# main.net
KiCad netlist of a schematic drawn in Altium Designer
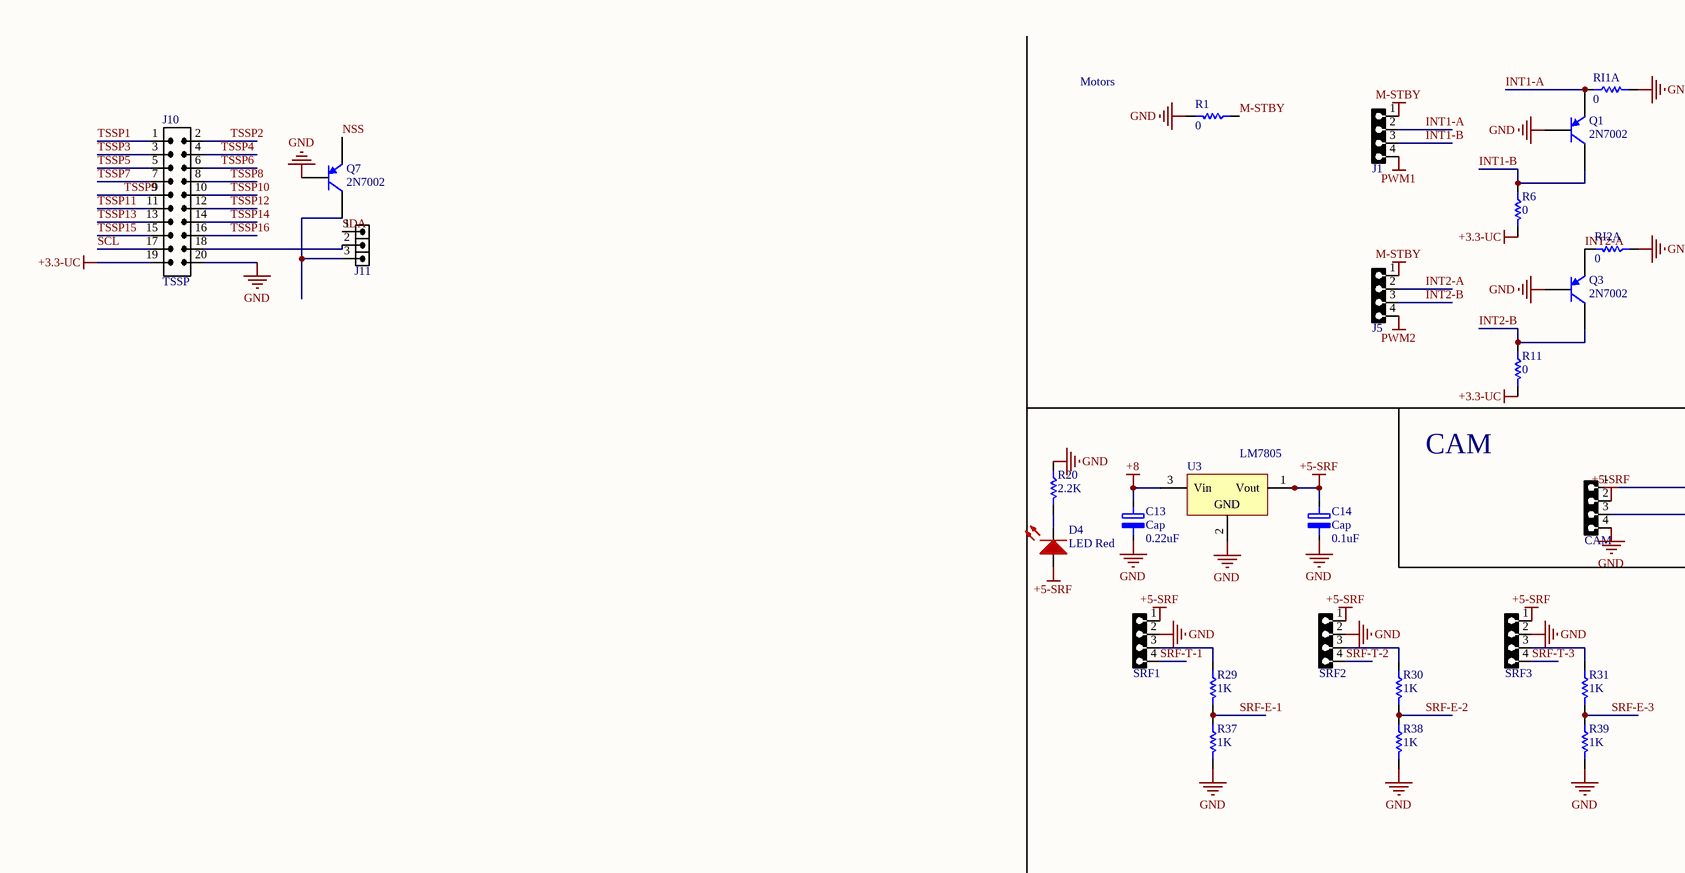
[diagram p0: main.SchDoc, top left]
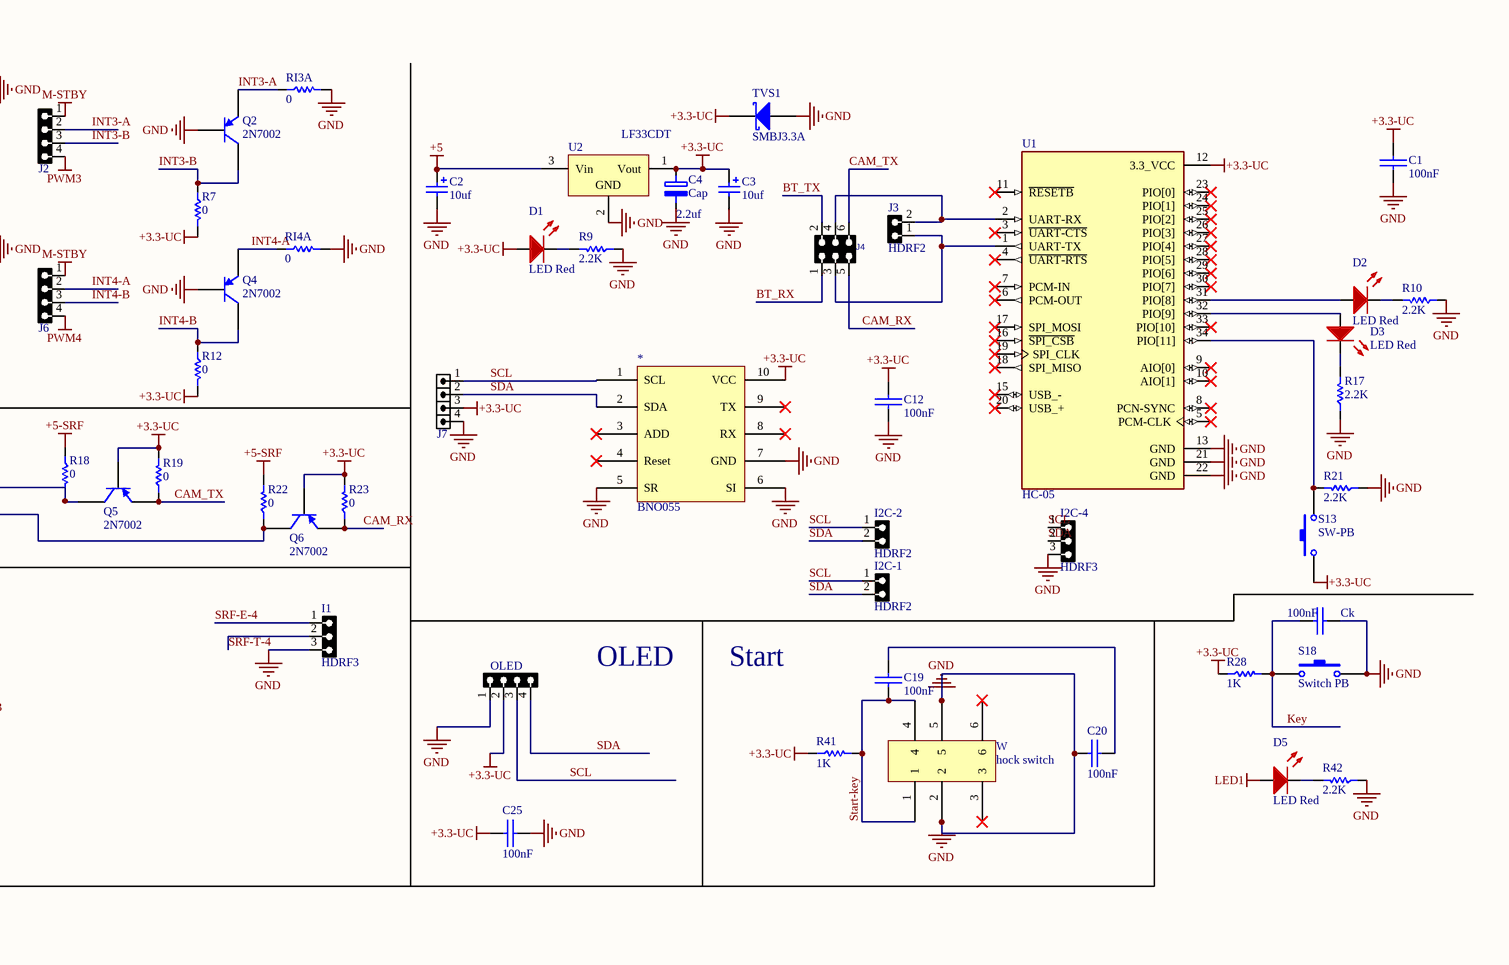
[diagram p1: main.SchDoc, top right]
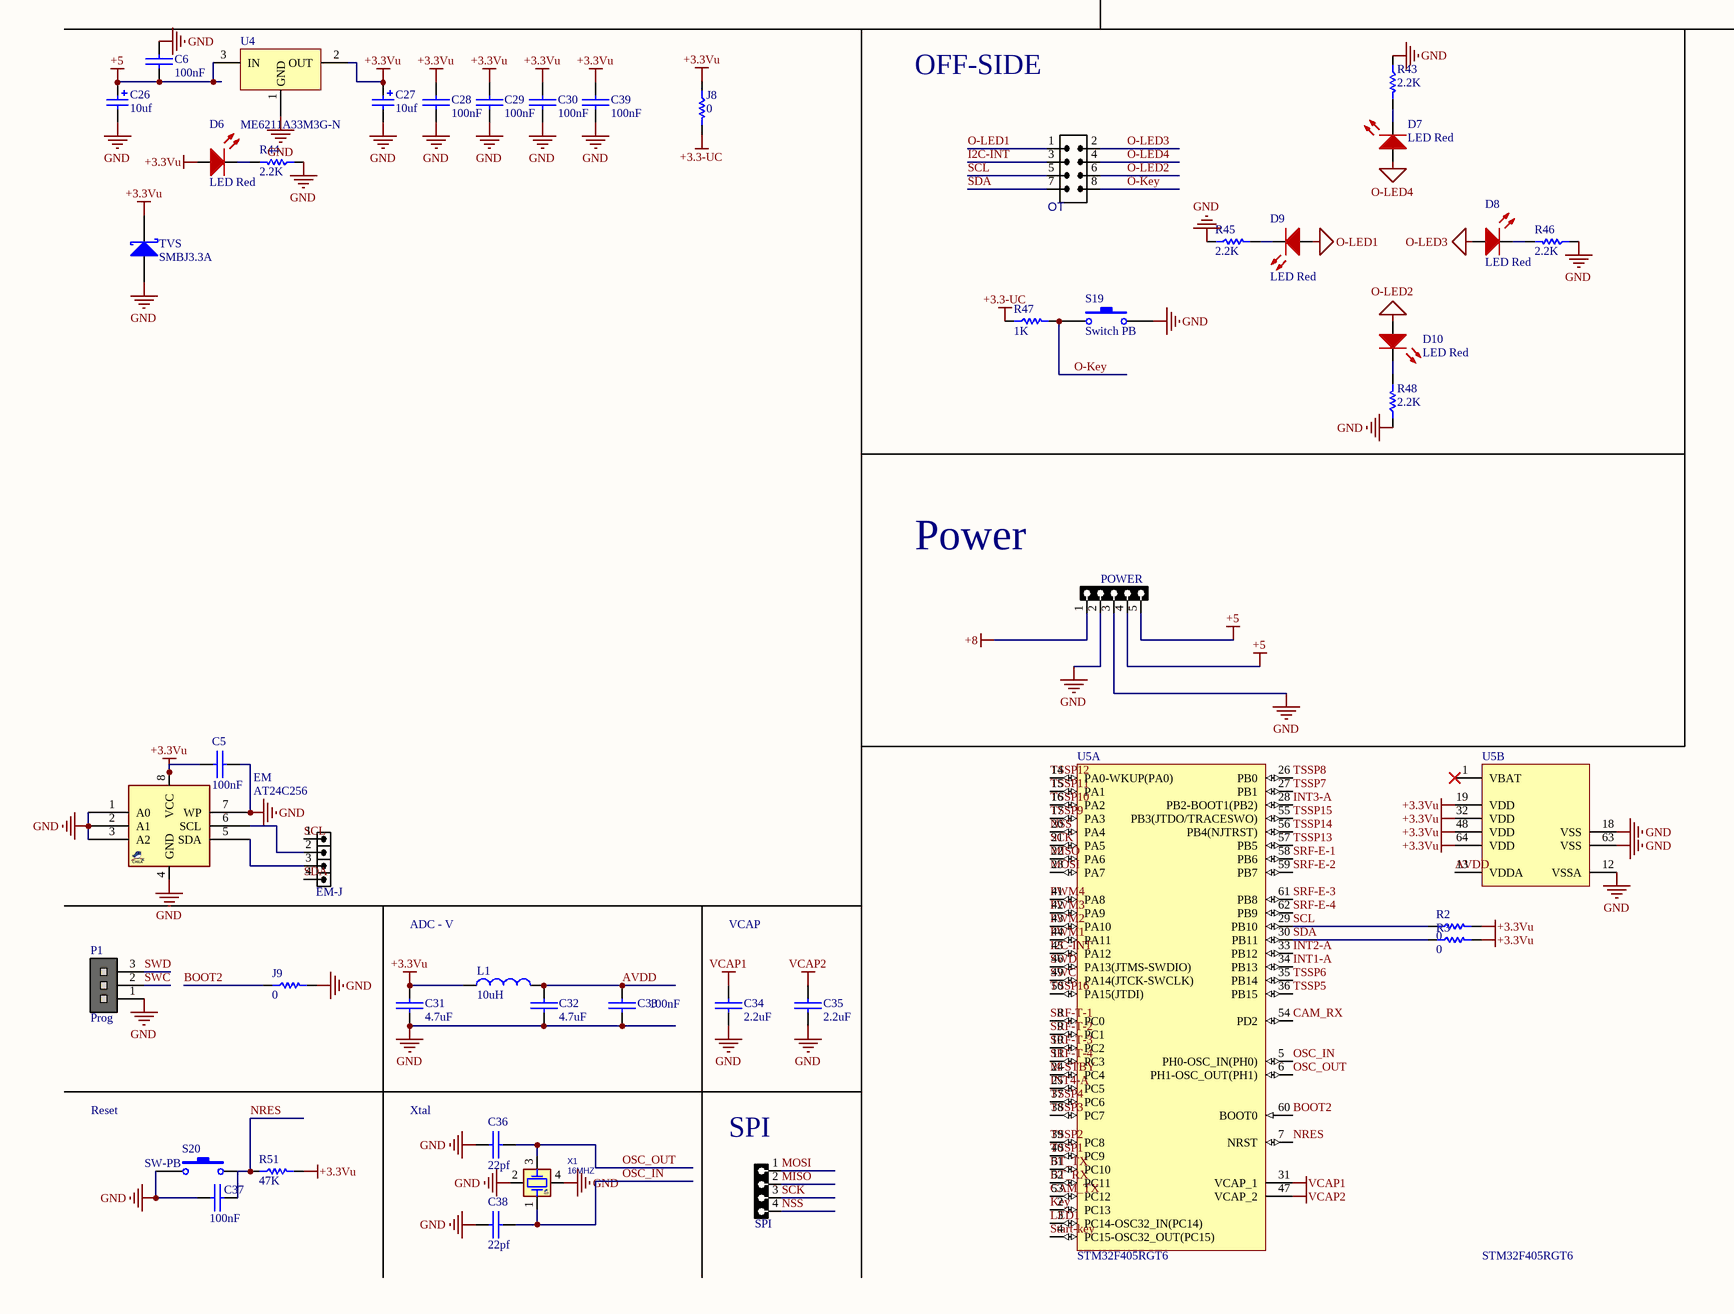
[diagram p2: main.SchDoc, bottom left]

(export (version "E")
  (design (tool "Eeschema 10.0.6"))
  (components
    (comp (ref "*") (value "BNO055") (footprint "BNO055") (libsource (lib "MA01") (part "BNO055")))
    (comp (ref "C1")
      (value "100nF")
      (footprint "SMD_CAP_0805")
      (description "Bipolar Capacitor")
      (fields (field (name "VOLTAGE") "100V") (field (name "DESIGNER") "Saeid Jorablo"))
      (libsource (lib "My Library") (part "Cap-Bipolar"))
    )
    (comp (ref "C2")
      (value "10uf")
      (footprint "Cap_A")
      (description "Solid Tantalum Chip Capacitor, Standard T491 Series - Industrial Grade")
      (fields (field (name "Comment") "Cap_tan") (field (name "PUBLISHER") "Altium Limited"))
      (libsource (lib "AYRIC Library") (part "Tantalum Cap"))
    )
    (comp (ref "C3")
      (value "10uf")
      (footprint "Cap_A")
      (description "Solid Tantalum Chip Capacitor, Standard T491 Series - Industrial Grade")
      (fields (field (name "Comment") "Cap_tan") (field (name "PUBLISHER") "Altium Limited"))
      (libsource (lib "AYRIC Library") (part "Tantalum Cap"))
    )
    (comp (ref "C4")
      (value "Cap")
      (footprint "Cap_E")
      (description "Polarized Capacitor (Radial)")
      (fields (field (name "ALTIUM_VALUE") "2.2uf"))
      (libsource (lib "AYRIC Library") (part "Cap_pol"))
    )
    (comp (ref "C5")
      (value "100nF")
      (footprint "C0603")
      (description "Bipolar Capacitor")
      (fields (field (name "VOLTAGE") "100V") (field (name "DESIGNER") "Saeid Jorablo"))
      (libsource (lib "My Library") (part "Cap-Bipolar"))
    )
    (comp (ref "C6")
      (value "100nF")
      (footprint "SMD_CAP_0805")
      (description "Bipolar Capacitor")
      (fields (field (name "VOLTAGE") "100V") (field (name "DESIGNER") "Saeid Jorablo"))
      (libsource (lib "My Library") (part "Cap-Bipolar"))
    )
    (comp (ref "C12")
      (value "100nF")
      (footprint "SMD_CAP_0805")
      (description "Bipolar Capacitor")
      (fields (field (name "VOLTAGE") "100V") (field (name "DESIGNER") "Saeid Jorablo"))
      (libsource (lib "My Library") (part "Cap-Bipolar"))
    )
    (comp (ref "C13")
      (value "Cap")
      (footprint "Cap1_(2mm)")
      (description "Polarized Capacitor (Radial)")
      (fields (field (name "C13") "0.22uF"))
      (libsource (lib "AYRIC Library") (part "Cap_pol"))
    )
    (comp (ref "C14")
      (value "Cap")
      (footprint "Cap1_(2mm)")
      (description "Polarized Capacitor (Radial)")
      (fields (field (name "C14") "0.1uF"))
      (libsource (lib "AYRIC Library") (part "Cap_pol"))
    )
    (comp (ref "C19")
      (value "100nF")
      (footprint "SMD_CAP_0805")
      (description "Bipolar Capacitor")
      (fields (field (name "VOLTAGE") "100V") (field (name "DESIGNER") "Saeid Jorablo"))
      (libsource (lib "My Library") (part "Cap-Bipolar"))
    )
    (comp (ref "C20")
      (value "100nF")
      (footprint "SMD_CAP_0805")
      (description "Bipolar Capacitor")
      (fields (field (name "VOLTAGE") "100V") (field (name "DESIGNER") "Saeid Jorablo"))
      (libsource (lib "My Library") (part "Cap-Bipolar"))
    )
    (comp (ref "C25")
      (value "100nF")
      (footprint "SMD_CAP_0805")
      (description "Bipolar Capacitor")
      (fields (field (name "VOLTAGE") "100V") (field (name "DESIGNER") "Saeid Jorablo"))
      (libsource (lib "My Library") (part "Cap-Bipolar"))
    )
    (comp (ref "C26")
      (value "10uf")
      (footprint "Cap_A")
      (description "Solid Tantalum Chip Capacitor, Standard T491 Series - Industrial Grade")
      (fields (field (name "Comment") "Cap_tan") (field (name "PUBLISHER") "Altium Limited"))
      (libsource (lib "AYRIC Library") (part "Tantalum Cap"))
    )
    (comp (ref "C27")
      (value "10uf")
      (footprint "Cap_A")
      (description "Solid Tantalum Chip Capacitor, Standard T491 Series - Industrial Grade")
      (fields (field (name "Comment") "Cap_tan") (field (name "PUBLISHER") "Altium Limited"))
      (libsource (lib "AYRIC Library") (part "Tantalum Cap"))
    )
    (comp (ref "C28")
      (value "100nF")
      (footprint "C0603")
      (description "Bipolar Capacitor")
      (fields (field (name "VOLTAGE") "100V") (field (name "DESIGNER") "Saeid Jorablo"))
      (libsource (lib "My Library") (part "Cap-Bipolar"))
    )
    (comp (ref "C29")
      (value "100nF")
      (footprint "C0603")
      (description "Bipolar Capacitor")
      (fields (field (name "VOLTAGE") "100V") (field (name "DESIGNER") "Saeid Jorablo"))
      (libsource (lib "My Library") (part "Cap-Bipolar"))
    )
    (comp (ref "C30")
      (value "100nF")
      (footprint "C0603")
      (description "Bipolar Capacitor")
      (fields (field (name "VOLTAGE") "100V") (field (name "DESIGNER") "Saeid Jorablo"))
      (libsource (lib "My Library") (part "Cap-Bipolar"))
    )
    (comp (ref "C31")
      (value "4.7uF")
      (footprint "SMD_CAP_0805")
      (description "Bipolar Capacitor")
      (fields (field (name "VOLTAGE") "100V") (field (name "DESIGNER") "Saeid Jorablo"))
      (libsource (lib "My Library") (part "Cap-Bipolar"))
    )
    (comp (ref "C32")
      (value "4.7uF")
      (footprint "SMD_CAP_0805")
      (description "Bipolar Capacitor")
      (fields (field (name "VOLTAGE") "100V") (field (name "DESIGNER") "Saeid Jorablo"))
      (libsource (lib "My Library") (part "Cap-Bipolar"))
    )
    (comp (ref "C33")
      (value "100nF")
      (footprint "SMD_CAP_0805")
      (description "Bipolar Capacitor")
      (fields (field (name "VOLTAGE") "100V") (field (name "DESIGNER") "Saeid Jorablo"))
      (libsource (lib "My Library") (part "Cap-Bipolar"))
    )
    (comp (ref "C34")
      (value "2.2uF")
      (footprint "C0603")
      (description "Bipolar Capacitor")
      (fields (field (name "VOLTAGE") "100V") (field (name "DESIGNER") "Saeid Jorablo"))
      (libsource (lib "My Library") (part "Cap-Bipolar"))
    )
    (comp (ref "C35")
      (value "2.2uF")
      (footprint "C0603")
      (description "Bipolar Capacitor")
      (fields (field (name "VOLTAGE") "100V") (field (name "DESIGNER") "Saeid Jorablo"))
      (libsource (lib "My Library") (part "Cap-Bipolar"))
    )
    (comp (ref "C36")
      (value "22pf")
      (footprint "SMD_CAP_0805")
      (description "Bipolar Capacitor")
      (fields (field (name "VOLTAGE") "100V") (field (name "DESIGNER") "Saeid Jorablo"))
      (libsource (lib "My Library") (part "Cap-Bipolar"))
    )
    (comp (ref "C37")
      (value "100nF")
      (footprint "SMD_CAP_0805")
      (description "Bipolar Capacitor")
      (fields (field (name "VOLTAGE") "100V") (field (name "DESIGNER") "Saeid Jorablo"))
      (libsource (lib "My Library") (part "Cap-Bipolar"))
    )
    (comp (ref "C38")
      (value "22pf")
      (footprint "SMD_CAP_0805")
      (description "Bipolar Capacitor")
      (fields (field (name "VOLTAGE") "100V") (field (name "DESIGNER") "Saeid Jorablo"))
      (libsource (lib "My Library") (part "Cap-Bipolar"))
    )
    (comp (ref "C39")
      (value "100nF")
      (footprint "C0603")
      (description "Bipolar Capacitor")
      (fields (field (name "VOLTAGE") "100V") (field (name "DESIGNER") "Saeid Jorablo"))
      (libsource (lib "My Library") (part "Cap-Bipolar"))
    )
    (comp (ref "CAM")
      (value "HDRF4")
      (footprint "HDR_F_1X4")
      (description "CONN, HEADER, Female, pitch: 2.54mm, 4POS")
      (libsource (lib "conn_header") (part "HDR_F_1X4"))
    )
    (comp (ref "Ck")
      (value "100nF")
      (footprint "SMD_CAP_0805")
      (description "Bipolar Capacitor")
      (fields (field (name "VOLTAGE") "100V") (field (name "DESIGNER") "Saeid Jorablo"))
      (libsource (lib "My Library") (part "Cap-Bipolar"))
    )
    (comp (ref "D1")
      (value "LED Red")
      (footprint "LED_Red_1206")
      (libsource (lib "AYRIC Library") (part "LED Red"))
    )
    (comp (ref "D2")
      (value "LED Red")
      (footprint "LED_Red_1206")
      (libsource (lib "AYRIC Library") (part "LED Red"))
    )
    (comp (ref "D3")
      (value "LED Red")
      (footprint "LED_Red_1206")
      (libsource (lib "AYRIC Library") (part "LED Red"))
    )
    (comp (ref "D4")
      (value "LED Red")
      (footprint "LED_Red_1206")
      (libsource (lib "AYRIC Library") (part "LED Red"))
    )
    (comp (ref "D5")
      (value "LED Red")
      (footprint "LED_Red_1206")
      (libsource (lib "AYRIC Library") (part "LED Red"))
    )
    (comp (ref "D6")
      (value "LED Red")
      (footprint "LED_Red_1206")
      (libsource (lib "AYRIC Library") (part "LED Red"))
    )
    (comp (ref "D7")
      (value "LED Red")
      (footprint "LED_Red_1206")
      (libsource (lib "AYRIC Library") (part "LED Red"))
    )
    (comp (ref "D8")
      (value "LED Red")
      (footprint "LED_Red_1206")
      (libsource (lib "AYRIC Library") (part "LED Red"))
    )
    (comp (ref "D9")
      (value "LED Red")
      (footprint "LED_Red_1206")
      (libsource (lib "AYRIC Library") (part "LED Red"))
    )
    (comp (ref "D10")
      (value "LED Red")
      (footprint "LED_Red_1206")
      (libsource (lib "AYRIC Library") (part "LED Red"))
    )
    (comp (ref "EM")
      (value "AT24C256")
      (footprint "SO_8")
      (description "EEPROM, I2C")
      (libsource (lib "memory_eeprom_I2C") (part "EEPROM_I2C_AT24C256_SOP8"))
    )
    (comp (ref "EM-J")
      (value "HDR4")
      (footprint "HDR1SE_M_1X4")
      (description "HEADER, 1mm pitch, test, SMD")
      (libsource (lib "conn_header") (part "HDRTST_1X4"))
    )
    (comp (ref "I1")
      (value "HDRF3")
      (footprint "HDR_F_1X3")
      (description "CONN, HEADER, Female, pitch: 2.54mm, 3POS")
      (libsource (lib "conn_header") (part "HDR_F_1X3"))
    )
    (comp (ref "I2C-1")
      (value "HDRF2")
      (footprint "HDR_F_1X2")
      (description "CONN, HEADER, Female, pitch: 2.54mm, 2POS")
      (libsource (lib "") (part "HDR_F_1X2_1"))
    )
    (comp (ref "I2C-2")
      (value "HDRF2")
      (footprint "HDR_F_1X2")
      (description "CONN, HEADER, Female, pitch: 2.54mm, 2POS")
      (libsource (lib "") (part "HDR_F_1X2_1"))
    )
    (comp (ref "I2C-4")
      (value "HDRF3")
      (footprint "HDR_F_1X3")
      (description "CONN, HEADER, Female, pitch: 2.54mm, 3POS")
      (libsource (lib "conn_header") (part "HDR_F_1X3"))
    )
    (comp (ref "J1")
      (value "HDRF4")
      (footprint "HDR_F_1X4")
      (description "CONN, HEADER, Female, pitch: 2.54mm, 4POS")
      (libsource (lib "conn_header") (part "HDR_F_1X4"))
    )
    (comp (ref "J2")
      (value "HDRF4")
      (footprint "HDR_F_1X4")
      (description "CONN, HEADER, Female, pitch: 2.54mm, 4POS")
      (libsource (lib "conn_header") (part "HDR_F_1X4"))
    )
    (comp (ref "J3")
      (value "HDRF2")
      (footprint "HDR_F_1X2")
      (description "CONN, HEADER, Female, pitch: 2.54mm, 2POS")
      (libsource (lib "conn_header") (part "HDR_F_1X2"))
    )
    (comp (ref "J4")
      (value "HDRF_2X3")
      (footprint "HDR_F_2X3")
      (description "CONN, HEADER, Female, pitch: 2.54mm, 6POS")
      (fields (field (name "MANF_P#") "MANF_PART#") (field (name "MANF") "MANF"))
      (libsource (lib "conn_header") (part "HDR_F_2X3"))
    )
    (comp (ref "J5")
      (value "HDRF4")
      (footprint "HDR_F_1X4")
      (description "CONN, HEADER, Female, pitch: 2.54mm, 4POS")
      (libsource (lib "conn_header") (part "HDR_F_1X4"))
    )
    (comp (ref "J6")
      (value "HDRF4")
      (footprint "HDR_F_1X4")
      (description "CONN, HEADER, Female, pitch: 2.54mm, 4POS")
      (libsource (lib "conn_header") (part "HDR_F_1X4"))
    )
    (comp (ref "J7")
      (value "HDR1X4")
      (footprint "HDR_M_1X4")
      (description "CONN, HEADER, Male, pitch: 2.54mm, 4POS")
      (libsource (lib "conn_header") (part "HDR_M_1X4"))
    )
    (comp (ref "J8")
      (value "0")
      (footprint "RES 0805 (2012X06L)")
      (description "Resistor")
      (libsource (lib "My Library") (part "Resistor"))
    )
    (comp (ref "J9")
      (value "0")
      (footprint "RES 0603 (1608X06L)")
      (description "Resistor")
      (libsource (lib "My Library") (part "Resistor"))
    )
    (comp (ref "J10")
      (value "TSSP")
      (footprint "IDC_2X10")
      (description "CONN, IDC, Male, pitch: 2.54mm, 20POS")
      (libsource (lib "conn_header_idc") (part "IDC_2X10"))
    )
    (comp (ref "J11")
      (value "HDR3")
      (footprint "HDR1SE_M_1X3")
      (description "HEADER, 1mm pitch, test, SMD")
      (libsource (lib "conn_header") (part "HDRTST_1X3"))
    )
    (comp (ref "L1")
      (value "10uH")
      (footprint "Capacitor_805")
      (fields (field (name "Comment") "Inductor") (field (name "PUBLISHER") "Altium Limited"))
      (libsource (lib "AYRIC Library") (part "Inductor"))
    )
    (comp (ref "OLED")
      (value "HDRF4")
      (footprint "OLED64*128")
      (description "CONN, HEADER, Female, pitch: 2.54mm, 4POS")
      (libsource (lib "") (part "HDR_F_1X4_1"))
    )
    (comp (ref "OT")
      (value "IDC_2X4")
      (footprint "IDC_2X4")
      (description "CONN, IDC, Male, pitch: 2.54mm, 8POS")
      (libsource (lib "conn_header_idc") (part "IDC_2X4"))
    )
    (comp (ref "P1")
      (value "Prog")
      (footprint "HDR 1X3")
      (description "Header, 3-Pin")
      (libsource (lib "Ayric connectors") (part "Header 3"))
    )
    (comp (ref "POWER")
      (value "HDRF5")
      (footprint "HDR_F_1X5")
      (description "CONN, HEADER, Female, pitch: 2.54mm, 5POS")
      (libsource (lib "conn_header") (part "HDR_F_1X5"))
    )
    (comp (ref "Q1")
      (value "2N7002")
      (footprint "SOT23_BEC_M")
      (description "PNP Bipolar Transistor")
      (fields (field (name "PUBLISHER") "Altium Limited"))
      (libsource (lib "My Library") (part "PNP"))
    )
    (comp (ref "Q2")
      (value "2N7002")
      (footprint "SOT23_BEC_M")
      (description "PNP Bipolar Transistor")
      (fields (field (name "PUBLISHER") "Altium Limited"))
      (libsource (lib "My Library") (part "PNP"))
    )
    (comp (ref "Q3")
      (value "2N7002")
      (footprint "SOT23_BEC_M")
      (description "PNP Bipolar Transistor")
      (fields (field (name "PUBLISHER") "Altium Limited"))
      (libsource (lib "My Library") (part "PNP"))
    )
    (comp (ref "Q4")
      (value "2N7002")
      (footprint "SOT23_BEC_M")
      (description "PNP Bipolar Transistor")
      (fields (field (name "PUBLISHER") "Altium Limited"))
      (libsource (lib "My Library") (part "PNP"))
    )
    (comp (ref "Q5")
      (value "2N7002")
      (footprint "SOT23_BEC_M")
      (description "PNP Bipolar Transistor")
      (fields (field (name "PUBLISHER") "Altium Limited"))
      (libsource (lib "My Library") (part "PNP"))
    )
    (comp (ref "Q6")
      (value "2N7002")
      (footprint "SOT23_BEC_M")
      (description "PNP Bipolar Transistor")
      (fields (field (name "PUBLISHER") "Altium Limited"))
      (libsource (lib "My Library") (part "PNP"))
    )
    (comp (ref "Q7")
      (value "2N7002")
      (footprint "SOT23_BEC_M")
      (description "PNP Bipolar Transistor")
      (fields (field (name "PUBLISHER") "Altium Limited"))
      (libsource (lib "My Library") (part "PNP"))
    )
    (comp (ref "R1")
      (value "0")
      (footprint "RES 0805 (2012X06L)")
      (description "Resistor")
      (libsource (lib "My Library") (part "Resistor"))
    )
    (comp (ref "R2")
      (value "0")
      (footprint "RES 1206 (3216X08L)")
      (description "Resistor")
      (libsource (lib "My Library") (part "Resistor"))
    )
    (comp (ref "R3")
      (value "0")
      (footprint "RES 1206 (3216X08L)")
      (description "Resistor")
      (libsource (lib "My Library") (part "Resistor"))
    )
    (comp (ref "R6")
      (value "0")
      (footprint "RES 0805 (2012X06L)")
      (description "Resistor")
      (libsource (lib "My Library") (part "Resistor"))
    )
    (comp (ref "R7")
      (value "0")
      (footprint "RES 0805 (2012X06L)")
      (description "Resistor")
      (libsource (lib "My Library") (part "Resistor"))
    )
    (comp (ref "R9")
      (value "2.2K")
      (footprint "RES 0805 (2012X06L)")
      (description "Resistor")
      (libsource (lib "My Library") (part "Resistor"))
    )
    (comp (ref "R10")
      (value "2.2K")
      (footprint "RES 0805 (2012X06L)")
      (description "Resistor")
      (libsource (lib "My Library") (part "Resistor"))
    )
    (comp (ref "R11")
      (value "0")
      (footprint "RES 0805 (2012X06L)")
      (description "Resistor")
      (libsource (lib "My Library") (part "Resistor"))
    )
    (comp (ref "R12")
      (value "0")
      (footprint "RES 0805 (2012X06L)")
      (description "Resistor")
      (libsource (lib "My Library") (part "Resistor"))
    )
    (comp (ref "R17")
      (value "2.2K")
      (footprint "RES 0805 (2012X06L)")
      (description "Resistor")
      (libsource (lib "My Library") (part "Resistor"))
    )
    (comp (ref "R18")
      (value "0")
      (footprint "RES 0805 (2012X06L)")
      (description "Resistor")
      (libsource (lib "My Library") (part "Resistor"))
    )
    (comp (ref "R19")
      (value "0")
      (footprint "RES 0805 (2012X06L)")
      (description "Resistor")
      (libsource (lib "My Library") (part "Resistor"))
    )
    (comp (ref "R20")
      (value "2.2K")
      (footprint "RES 0805 (2012X06L)")
      (description "Resistor")
      (libsource (lib "My Library") (part "Resistor"))
    )
    (comp (ref "R21")
      (value "2.2K")
      (footprint "RES 0805 (2012X06L)")
      (description "Resistor")
      (libsource (lib "My Library") (part "Resistor"))
    )
    (comp (ref "R22")
      (value "0")
      (footprint "RES 0805 (2012X06L)")
      (description "Resistor")
      (libsource (lib "My Library") (part "Resistor"))
    )
    (comp (ref "R23")
      (value "0")
      (footprint "RES 0805 (2012X06L)")
      (description "Resistor")
      (libsource (lib "My Library") (part "Resistor"))
    )
    (comp (ref "R28")
      (value "1K")
      (footprint "RES 0805 (2012X06L)")
      (description "Resistor")
      (libsource (lib "My Library") (part "Resistor"))
    )
    (comp (ref "R29")
      (value "1K")
      (footprint "RES 0805 (2012X06L)")
      (description "Resistor")
      (libsource (lib "My Library") (part "Resistor"))
    )
    (comp (ref "R30")
      (value "1K")
      (footprint "RES 0805 (2012X06L)")
      (description "Resistor")
      (libsource (lib "My Library") (part "Resistor"))
    )
    (comp (ref "R31")
      (value "1K")
      (footprint "RES 0805 (2012X06L)")
      (description "Resistor")
      (libsource (lib "My Library") (part "Resistor"))
    )
    (comp (ref "R37")
      (value "1K")
      (footprint "RES 0805 (2012X06L)")
      (description "Resistor")
      (libsource (lib "My Library") (part "Resistor"))
    )
    (comp (ref "R38")
      (value "1K")
      (footprint "RES 0805 (2012X06L)")
      (description "Resistor")
      (libsource (lib "My Library") (part "Resistor"))
    )
    (comp (ref "R39")
      (value "1K")
      (footprint "RES 0805 (2012X06L)")
      (description "Resistor")
      (libsource (lib "My Library") (part "Resistor"))
    )
    (comp (ref "R41")
      (value "1K")
      (footprint "RES 0805 (2012X06L)")
      (description "Resistor")
      (libsource (lib "My Library") (part "Resistor"))
    )
    (comp (ref "R42")
      (value "2.2K")
      (footprint "RES 0805 (2012X06L)")
      (description "Resistor")
      (libsource (lib "My Library") (part "Resistor"))
    )
    (comp (ref "R43")
      (value "2.2K")
      (footprint "RES 0805 (2012X06L)")
      (description "Resistor")
      (libsource (lib "My Library") (part "Resistor"))
    )
    (comp (ref "R44")
      (value "2.2K")
      (footprint "RES 0805 (2012X06L)")
      (description "Resistor")
      (libsource (lib "My Library") (part "Resistor"))
    )
    (comp (ref "R45")
      (value "2.2K")
      (footprint "RES 0805 (2012X06L)")
      (description "Resistor")
      (libsource (lib "My Library") (part "Resistor"))
    )
    (comp (ref "R46")
      (value "2.2K")
      (footprint "RES 0805 (2012X06L)")
      (description "Resistor")
      (libsource (lib "My Library") (part "Resistor"))
    )
    (comp (ref "R47")
      (value "1K")
      (footprint "RES 0805 (2012X06L)")
      (description "Resistor")
      (libsource (lib "My Library") (part "Resistor"))
    )
    (comp (ref "R48")
      (value "2.2K")
      (footprint "RES 0805 (2012X06L)")
      (description "Resistor")
      (libsource (lib "My Library") (part "Resistor"))
    )
    (comp (ref "R51")
      (value "47K")
      (footprint "RES 0805 (2012X06L)")
      (description "Resistor")
      (libsource (lib "My Library") (part "Resistor"))
    )
    (comp (ref "RI1A")
      (value "0")
      (footprint "RES 0805 (2012X06L)")
      (description "Resistor")
      (libsource (lib "My Library") (part "Resistor"))
    )
    (comp (ref "RI2A")
      (value "0")
      (footprint "RES 0805 (2012X06L)")
      (description "Resistor")
      (libsource (lib "My Library") (part "Resistor"))
    )
    (comp (ref "RI3A")
      (value "0")
      (footprint "RES 0805 (2012X06L)")
      (description "Resistor")
      (libsource (lib "My Library") (part "Resistor"))
    )
    (comp (ref "RI4A")
      (value "0")
      (footprint "RES 0805 (2012X06L)")
      (description "Resistor")
      (libsource (lib "My Library") (part "Resistor"))
    )
    (comp (ref "S13")
      (value "SW-PB")
      (footprint "SPST")
      (description "Switch")
      (libsource (lib "AYRIC Library") (part "SW-PB"))
    )
    (comp (ref "S18")
      (value "Switch PB")
      (footprint "SW-PB")
      (description "Push Button Switch")
      (libsource (lib "My Library") (part "Switch PB"))
    )
    (comp (ref "S19")
      (value "Switch PB")
      (footprint "SW-PB")
      (description "Push Button Switch")
      (libsource (lib "My Library") (part "Switch PB"))
    )
    (comp (ref "S20")
      (value "SW-PB")
      (footprint "SPST")
      (description "Switch")
      (libsource (lib "AYRIC Library") (part "SW-PB"))
    )
    (comp (ref "SPI")
      (value "HDRF4")
      (footprint "HDR_F_1X4")
      (description "CONN, HEADER, Female, pitch: 2.54mm, 4POS")
      (libsource (lib "conn_header") (part "HDR_F_1X4"))
    )
    (comp (ref "SRF1")
      (value "HDRF4")
      (footprint "HDR_F_1X4")
      (description "CONN, HEADER, Female, pitch: 2.54mm, 4POS")
      (libsource (lib "conn_header") (part "HDR_F_1X4"))
    )
    (comp (ref "SRF2")
      (value "HDRF4")
      (footprint "HDR_F_1X4")
      (description "CONN, HEADER, Female, pitch: 2.54mm, 4POS")
      (libsource (lib "conn_header") (part "HDR_F_1X4"))
    )
    (comp (ref "SRF3")
      (value "HDRF4")
      (footprint "HDR_F_1X4")
      (description "CONN, HEADER, Female, pitch: 2.54mm, 4POS")
      (libsource (lib "conn_header") (part "HDR_F_1X4"))
    )
    (comp (ref "TVS")
      (value "SMBJ3.3A")
      (footprint "Diode_SS34")
      (description "Schottky diode")
      (libsource (lib "AYRIC Library") (part "1N5819"))
    )
    (comp (ref "TVS1")
      (value "SMBJ3.3A")
      (footprint "Diode_SS34")
      (description "Schottky diode")
      (libsource (lib "AYRIC Library") (part "1N5819"))
    )
    (comp (ref "U1")
      (value "HC-05")
      (footprint "HC-05")
      (description "Bluetooth to Serial Port Module")
      (libsource (lib "HC-05") (part "HC-05"))
    )
    (comp (ref "U2") (value "LF33CDT") (footprint "TO 252") (libsource (lib "AYRIC Library") (part "LM7805")))
    (comp (ref "U3") (value "LM7805") (footprint "TO 252") (libsource (lib "AYRIC Library") (part "LM7805")))
    (comp (ref "U4")
      (value "ME6211A33M3G-N")
      (footprint "SOT23_3")
      (description "IC, Regulator, Linear LDO ,Low noise")
      (libsource (lib "Schlib-lib") (part "ME6211A33M3G-N"))
    )
    (comp (ref "U5")
      (value "STM32F405RGT6")
      (footprint "STM-LQFP64_N")
      (fields (field (name "MANUFACTURER") "STMicroelectronics"))
      (libsource (lib "Schlib1") (part "STM32F405RGT6"))
    )
    (comp (ref "W")
      (value "hock switch")
      (footprint "hock switch")
      (libsource (lib "MA01") (part "hock switch"))
    )
    (comp (ref "X1")
      (value "16MHZ")
      (footprint "XTL_4_3225")
      (description "Crystal 24MHz")
      (fields (field (name "MANF") "EPSON") (field (name "MANF_P#") "TSX-3225 24.0000MF10Z-C3"))
      (libsource (lib "Schlib-lib") (part "XTL_16MHz_3225"))
    )
  )
  (nets
    (net (code "1") (name "+3.3-UC") (class "Default")
      (node (ref "*") (pin "10") (pinfunction "VCC_10") (pintype "passive"))
      (node (ref "C1") (pin "1") (pinfunction "+_1") (pintype "passive"))
      (node (ref "C12") (pin "1") (pinfunction "+_1") (pintype "passive"))
      (node (ref "C25") (pin "1") (pinfunction "+_1") (pintype "passive"))
      (node (ref "C3") (pin "1") (pinfunction "1_1") (pintype "passive"))
      (node (ref "C4") (pin "1") (pinfunction "1_1") (pintype "passive"))
      (node (ref "D1") (pin "1") (pinfunction "A_1") (pintype "passive"))
      (node (ref "J10") (pin "19") (pinfunction "19_19") (pintype "passive"))
      (node (ref "J7") (pin "3") (pinfunction "3_3") (pintype "passive"))
      (node (ref "J8") (pin "2") (pinfunction "2_2") (pintype "passive"))
      (node (ref "OLED") (pin "2") (pinfunction "2_2") (pintype "passive"))
      (node (ref "Q5") (pin "1") (pinfunction "B_1") (pintype "passive"))
      (node (ref "Q6") (pin "1") (pinfunction "B_1") (pintype "passive"))
      (node (ref "R11") (pin "2") (pinfunction "2_2") (pintype "passive"))
      (node (ref "R12") (pin "2") (pinfunction "2_2") (pintype "passive"))
      (node (ref "R19") (pin "2") (pinfunction "2_2") (pintype "passive"))
      (node (ref "R23") (pin "2") (pinfunction "2_2") (pintype "passive"))
      (node (ref "R28") (pin "1") (pinfunction "1_1") (pintype "passive"))
      (node (ref "R41") (pin "1") (pinfunction "1_1") (pintype "passive"))
      (node (ref "R47") (pin "1") (pinfunction "1_1") (pintype "passive"))
      (node (ref "R6") (pin "2") (pinfunction "2_2") (pintype "passive"))
      (node (ref "R7") (pin "2") (pinfunction "2_2") (pintype "passive"))
      (node (ref "S13") (pin "1") (pinfunction "1_1") (pintype "passive"))
      (node (ref "TVS1") (pin "2") (pinfunction "K_2") (pintype "passive"))
      (node (ref "U1") (pin "12") (pinfunction "3.3_VCC_12") (pintype "power_in"))
      (node (ref "U2") (pin "1") (pinfunction "Vout_1") (pintype "passive"))
    )
    (net (code "2") (name "+3.3Vu") (class "Default")
      (node (ref "C27") (pin "1") (pinfunction "1_1") (pintype "passive"))
      (node (ref "C28") (pin "1") (pinfunction "+_1") (pintype "passive"))
      (node (ref "C29") (pin "1") (pinfunction "+_1") (pintype "passive"))
      (node (ref "C30") (pin "1") (pinfunction "+_1") (pintype "passive"))
      (node (ref "C31") (pin "1") (pinfunction "+_1") (pintype "passive"))
      (node (ref "C39") (pin "1") (pinfunction "+_1") (pintype "passive"))
      (node (ref "C5") (pin "1") (pinfunction "+_1") (pintype "passive"))
      (node (ref "D6") (pin "1") (pinfunction "A_1") (pintype "passive"))
      (node (ref "EM") (pin "8") (pinfunction "VCC_8") (pintype "passive"))
      (node (ref "J8") (pin "1") (pinfunction "1_1") (pintype "passive"))
      (node (ref "L1") (pin "1") (pinfunction "1_1") (pintype "passive"))
      (node (ref "R2") (pin "2") (pinfunction "2_2") (pintype "passive"))
      (node (ref "R3") (pin "2") (pinfunction "2_2") (pintype "passive"))
      (node (ref "R51") (pin "2") (pinfunction "2_2") (pintype "passive"))
      (node (ref "TVS") (pin "2") (pinfunction "K_2") (pintype "passive"))
      (node (ref "U4") (pin "2") (pinfunction "OUT_2") (pintype "passive"))
      (node (ref "U5") (pin "19") (pinfunction "VDD_19") (pintype "power_in"))
      (node (ref "U5") (pin "32") (pinfunction "VDD_32") (pintype "power_in"))
      (node (ref "U5") (pin "48") (pinfunction "VDD_48") (pintype "power_in"))
      (node (ref "U5") (pin "64") (pinfunction "VDD_64") (pintype "power_in"))
    )
    (net (code "3") (name "+5") (class "Default")
      (node (ref "C2") (pin "1") (pinfunction "1_1") (pintype "passive"))
      (node (ref "C26") (pin "1") (pinfunction "1_1") (pintype "passive"))
      (node (ref "C6") (pin "2") (pinfunction "-_2") (pintype "passive"))
      (node (ref "POWER") (pin "4") (pinfunction "4_4") (pintype "passive"))
      (node (ref "POWER") (pin "5") (pinfunction "5_5") (pintype "passive"))
      (node (ref "U2") (pin "3") (pinfunction "Vin_3") (pintype "passive"))
      (node (ref "U4") (pin "3") (pinfunction "IN_3") (pintype "passive"))
    )
    (net (code "4") (name "+5-SRF") (class "Default")
      (node (ref "C14") (pin "1") (pinfunction "1_1") (pintype "passive"))
      (node (ref "CAM") (pin "2") (pinfunction "2_2") (pintype "passive"))
      (node (ref "D4") (pin "1") (pinfunction "A_1") (pintype "passive"))
      (node (ref "R18") (pin "1") (pinfunction "1_1") (pintype "passive"))
      (node (ref "R22") (pin "2") (pinfunction "2_2") (pintype "passive"))
      (node (ref "SRF1") (pin "1") (pinfunction "1_1") (pintype "passive"))
      (node (ref "SRF2") (pin "1") (pinfunction "1_1") (pintype "passive"))
      (node (ref "SRF3") (pin "1") (pinfunction "1_1") (pintype "passive"))
      (node (ref "U3") (pin "1") (pinfunction "Vout_1") (pintype "passive"))
    )
    (net (code "5") (name "+8") (class "Default")
      (node (ref "C13") (pin "1") (pinfunction "1_1") (pintype "passive"))
      (node (ref "POWER") (pin "1") (pinfunction "1_1") (pintype "passive"))
      (node (ref "U3") (pin "3") (pinfunction "Vin_3") (pintype "passive"))
    )
    (net (code "6") (name "/AVDD") (class "Default")
      (node (ref "C32") (pin "1") (pinfunction "+_1") (pintype "passive"))
      (node (ref "C33") (pin "1") (pinfunction "+_1") (pintype "passive"))
      (node (ref "L1") (pin "2") (pinfunction "2_2") (pintype "passive"))
      (node (ref "U5") (pin "13") (pinfunction "VDDA_13") (pintype "power_in"))
    )
    (net (code "7") (name "/BOOT2") (class "Default")
      (node (ref "J9") (pin "1") (pinfunction "1_1") (pintype "passive"))
      (node (ref "U5") (pin "60") (pinfunction "BOOT0_60") (pintype "input"))
    )
    (net (code "8") (name "/BT_RX") (class "Default")
      (node (ref "J4") (pin "1") (pinfunction "1_1") (pintype "passive"))
      (node (ref "U5") (pin "52") (pinfunction "PC11_52") (pintype "bidirectional"))
    )
    (net (code "9") (name "/BT_TX") (class "Default")
      (node (ref "J4") (pin "2") (pinfunction "2_2") (pintype "passive"))
      (node (ref "U5") (pin "51") (pinfunction "PC10_51") (pintype "bidirectional"))
    )
    (net (code "10") (name "/CAM_RX") (class "Default")
      (node (ref "J4") (pin "5") (pinfunction "5_5") (pintype "passive"))
      (node (ref "Q6") (pin "2") (pinfunction "E_2") (pintype "passive"))
      (node (ref "R23") (pin "1") (pinfunction "1_1") (pintype "passive"))
      (node (ref "U5") (pin "54") (pinfunction "PD2_54") (pintype "bidirectional"))
    )
    (net (code "11") (name "/CAM_TX") (class "Default")
      (node (ref "J4") (pin "6") (pinfunction "6_6") (pintype "passive"))
      (node (ref "Q5") (pin "2") (pinfunction "E_2") (pintype "passive"))
      (node (ref "R19") (pin "1") (pinfunction "1_1") (pintype "passive"))
      (node (ref "U5") (pin "53") (pinfunction "PC12_53") (pintype "bidirectional"))
    )
    (net (code "12") (name "/I2C-INT") (class "Default")
      (node (ref "OT") (pin "3") (pinfunction "3_3") (pintype "passive"))
      (node (ref "U5") (pin "45") (pinfunction "PA12_45") (pintype "bidirectional"))
    )
    (net (code "13") (name "/INT1-A") (class "Default")
      (node (ref "J1") (pin "2") (pinfunction "2_2") (pintype "passive"))
      (node (ref "Q1") (pin "2") (pinfunction "E_2") (pintype "passive"))
      (node (ref "RI1A") (pin "1") (pinfunction "1_1") (pintype "passive"))
      (node (ref "U5") (pin "34") (pinfunction "PB13_34") (pintype "bidirectional"))
    )
    (net (code "14") (name "/INT1-B") (class "Default")
      (node (ref "J1") (pin "3") (pinfunction "3_3") (pintype "passive"))
      (node (ref "Q1") (pin "3") (pinfunction "C_3") (pintype "passive"))
      (node (ref "R6") (pin "1") (pinfunction "1_1") (pintype "passive"))
    )
    (net (code "15") (name "/INT2-A") (class "Default")
      (node (ref "J5") (pin "2") (pinfunction "2_2") (pintype "passive"))
      (node (ref "Q3") (pin "2") (pinfunction "E_2") (pintype "passive"))
      (node (ref "RI2A") (pin "2") (pinfunction "2_2") (pintype "passive"))
      (node (ref "U5") (pin "33") (pinfunction "PB12_33") (pintype "bidirectional"))
    )
    (net (code "16") (name "/INT2-B") (class "Default")
      (node (ref "J5") (pin "3") (pinfunction "3_3") (pintype "passive"))
      (node (ref "Q3") (pin "3") (pinfunction "C_3") (pintype "passive"))
      (node (ref "R11") (pin "1") (pinfunction "1_1") (pintype "passive"))
    )
    (net (code "17") (name "/INT3-A") (class "Default")
      (node (ref "J2") (pin "2") (pinfunction "2_2") (pintype "passive"))
      (node (ref "Q2") (pin "2") (pinfunction "E_2") (pintype "passive"))
      (node (ref "RI3A") (pin "1") (pinfunction "1_1") (pintype "passive"))
      (node (ref "U5") (pin "28") (pinfunction "PB2-BOOT1(PB2)_28") (pintype "bidirectional"))
    )
    (net (code "18") (name "/INT3-B") (class "Default")
      (node (ref "J2") (pin "3") (pinfunction "3_3") (pintype "passive"))
      (node (ref "Q2") (pin "3") (pinfunction "C_3") (pintype "passive"))
      (node (ref "R7") (pin "1") (pinfunction "1_1") (pintype "passive"))
    )
    (net (code "19") (name "/INT4-A") (class "Default")
      (node (ref "J6") (pin "2") (pinfunction "2_2") (pintype "passive"))
      (node (ref "Q4") (pin "2") (pinfunction "E_2") (pintype "passive"))
      (node (ref "RI4A") (pin "1") (pinfunction "1_1") (pintype "passive"))
      (node (ref "U5") (pin "25") (pinfunction "PC5_25") (pintype "bidirectional"))
    )
    (net (code "20") (name "/INT4-B") (class "Default")
      (node (ref "J6") (pin "3") (pinfunction "3_3") (pintype "passive"))
      (node (ref "Q4") (pin "3") (pinfunction "C_3") (pintype "passive"))
      (node (ref "R12") (pin "1") (pinfunction "1_1") (pintype "passive"))
    )
    (net (code "21") (name "/Key") (class "Default")
      (node (ref "Ck") (pin "2") (pinfunction "-_2") (pintype "passive"))
      (node (ref "R28") (pin "2") (pinfunction "2_2") (pintype "passive"))
      (node (ref "S18") (pin "1") (pinfunction "1_1") (pintype "passive"))
      (node (ref "U5") (pin "2") (pinfunction "PC13_2") (pintype "bidirectional"))
    )
    (net (code "22") (name "/MISO") (class "Default")
      (node (ref "SPI") (pin "2") (pinfunction "2_2") (pintype "passive"))
      (node (ref "U5") (pin "22") (pinfunction "PA6_22") (pintype "bidirectional"))
    )
    (net (code "23") (name "/MOSI") (class "Default")
      (node (ref "SPI") (pin "1") (pinfunction "1_1") (pintype "passive"))
      (node (ref "U5") (pin "23") (pinfunction "PA7_23") (pintype "bidirectional"))
    )
    (net (code "24") (name "/NRES") (class "Default")
      (node (ref "C37") (pin "2") (pinfunction "-_2") (pintype "passive"))
      (node (ref "R51") (pin "1") (pinfunction "1_1") (pintype "passive"))
      (node (ref "S20") (pin "2") (pinfunction "2_2") (pintype "passive"))
      (node (ref "U5") (pin "7") (pinfunction "NRST_7") (pintype "bidirectional"))
    )
    (net (code "25") (name "/NSS") (class "Default")
      (node (ref "Q7") (pin "2") (pinfunction "E_2") (pintype "passive"))
      (node (ref "SPI") (pin "4") (pinfunction "4_4") (pintype "passive"))
      (node (ref "U5") (pin "20") (pinfunction "PA4_20") (pintype "bidirectional"))
    )
    (net (code "26") (name "/O-Key") (class "Default")
      (node (ref "OT") (pin "8") (pinfunction "8_8") (pintype "passive"))
      (node (ref "R47") (pin "2") (pinfunction "2_2") (pintype "passive"))
      (node (ref "S19") (pin "1") (pinfunction "1_1") (pintype "passive"))
    )
    (net (code "27") (name "/OSC_IN") (class "Default")
      (node (ref "C38") (pin "1") (pinfunction "+_1") (pintype "passive"))
      (node (ref "U5") (pin "5") (pinfunction "PH0-OSC_IN(PH0)_5") (pintype "bidirectional"))
      (node (ref "X1") (pin "1") (pinfunction "1_1") (pintype "passive"))
    )
    (net (code "28") (name "/OSC_OUT") (class "Default")
      (node (ref "C36") (pin "1") (pinfunction "+_1") (pintype "passive"))
      (node (ref "U5") (pin "6") (pinfunction "PH1-OSC_OUT(PH1)_6") (pintype "bidirectional"))
      (node (ref "X1") (pin "3") (pinfunction "2_3") (pintype "passive"))
    )
    (net (code "29") (name "/SCK") (class "Default")
      (node (ref "SPI") (pin "3") (pinfunction "3_3") (pintype "passive"))
      (node (ref "U5") (pin "21") (pinfunction "PA5_21") (pintype "bidirectional"))
    )
    (net (code "30") (name "/SCL") (class "Default")
      (node (ref "*") (pin "1") (pinfunction "SCL_1") (pintype "passive"))
      (node (ref "EM-J") (pin "1") (pinfunction "1_1") (pintype "passive"))
      (node (ref "I2C-1") (pin "1") (pinfunction "1_1") (pintype "passive"))
      (node (ref "I2C-2") (pin "1") (pinfunction "1_1") (pintype "passive"))
      (node (ref "I2C-4") (pin "1") (pinfunction "1_1") (pintype "passive"))
      (node (ref "J10") (pin "17") (pinfunction "17_17") (pintype "passive"))
      (node (ref "J7") (pin "1") (pinfunction "1_1") (pintype "passive"))
      (node (ref "OLED") (pin "3") (pinfunction "3_3") (pintype "passive"))
      (node (ref "OT") (pin "5") (pinfunction "5_5") (pintype "passive"))
      (node (ref "R2") (pin "1") (pinfunction "1_1") (pintype "passive"))
      (node (ref "U5") (pin "29") (pinfunction "PB10_29") (pintype "bidirectional"))
    )
    (net (code "31") (name "/SDA") (class "Default")
      (node (ref "*") (pin "2") (pinfunction "SDA_2") (pintype "passive"))
      (node (ref "EM-J") (pin "4") (pinfunction "4_4") (pintype "passive"))
      (node (ref "I2C-1") (pin "2") (pinfunction "2_2") (pintype "passive"))
      (node (ref "I2C-2") (pin "2") (pinfunction "2_2") (pintype "passive"))
      (node (ref "I2C-4") (pin "2") (pinfunction "2_2") (pintype "passive"))
      (node (ref "J11") (pin "1") (pinfunction "1_1") (pintype "passive"))
      (node (ref "J7") (pin "2") (pinfunction "2_2") (pintype "passive"))
      (node (ref "OLED") (pin "4") (pinfunction "4_4") (pintype "passive"))
      (node (ref "OT") (pin "7") (pinfunction "7_7") (pintype "passive"))
      (node (ref "R3") (pin "1") (pinfunction "1_1") (pintype "passive"))
      (node (ref "U5") (pin "30") (pinfunction "PB11_30") (pintype "bidirectional"))
    )
    (net (code "32") (name "/SRF-E-1") (class "Default")
      (node (ref "R29") (pin "2") (pinfunction "2_2") (pintype "passive"))
      (node (ref "R37") (pin "1") (pinfunction "1_1") (pintype "passive"))
      (node (ref "U5") (pin "58") (pinfunction "PB6_58") (pintype "bidirectional"))
    )
    (net (code "33") (name "/SRF-E-2") (class "Default")
      (node (ref "R30") (pin "2") (pinfunction "2_2") (pintype "passive"))
      (node (ref "R38") (pin "1") (pinfunction "1_1") (pintype "passive"))
      (node (ref "U5") (pin "59") (pinfunction "PB7_59") (pintype "bidirectional"))
    )
    (net (code "34") (name "/SRF-E-3") (class "Default")
      (node (ref "R31") (pin "2") (pinfunction "2_2") (pintype "passive"))
      (node (ref "R39") (pin "1") (pinfunction "1_1") (pintype "passive"))
      (node (ref "U5") (pin "61") (pinfunction "PB8_61") (pintype "bidirectional"))
    )
    (net (code "35") (name "/SRF-E-4") (class "Default")
      (node (ref "I1") (pin "1") (pinfunction "1_1") (pintype "passive"))
      (node (ref "U5") (pin "62") (pinfunction "PB9_62") (pintype "bidirectional"))
    )
    (net (code "36") (name "/SRF-T-1") (class "Default")
      (node (ref "SRF1") (pin "4") (pinfunction "4_4") (pintype "passive"))
      (node (ref "U5") (pin "8") (pinfunction "PC0_8") (pintype "bidirectional"))
    )
    (net (code "37") (name "/SRF-T-2") (class "Default")
      (node (ref "SRF2") (pin "4") (pinfunction "4_4") (pintype "passive"))
      (node (ref "U5") (pin "9") (pinfunction "PC1_9") (pintype "bidirectional"))
    )
    (net (code "38") (name "/SRF-T-3") (class "Default")
      (node (ref "SRF3") (pin "4") (pinfunction "4_4") (pintype "passive"))
      (node (ref "U5") (pin "10") (pinfunction "PC2_10") (pintype "bidirectional"))
    )
    (net (code "39") (name "/SRF-T-4") (class "Default")
      (node (ref "I1") (pin "2") (pinfunction "2_2") (pintype "passive"))
      (node (ref "U5") (pin "11") (pinfunction "PC3_11") (pintype "bidirectional"))
    )
    (net (code "40") (name "/SWC") (class "Default")
      (node (ref "P1") (pin "2") (pinfunction "2_2") (pintype "passive"))
      (node (ref "U5") (pin "49") (pinfunction "PA14(JTCK-SWCLK)_49") (pintype "bidirectional"))
    )
    (net (code "41") (name "/SWD") (class "Default")
      (node (ref "P1") (pin "3") (pinfunction "3_3") (pintype "passive"))
      (node (ref "U5") (pin "46") (pinfunction "PA13(JTMS-SWDIO)_46") (pintype "bidirectional"))
    )
    (net (code "42") (name "/Start-key") (class "Default")
      (node (ref "C19") (pin "1") (pinfunction "+_1") (pintype "passive"))
      (node (ref "R41") (pin "2") (pinfunction "2_2") (pintype "passive"))
      (node (ref "U5") (pin "4") (pinfunction "PC15-OSC32_OUT(PC15)_4") (pintype "bidirectional"))
      (node (ref "W") (pin "1") (pinfunction "1_1") (pintype "passive"))
      (node (ref "W") (pin "4") (pinfunction "4_4") (pintype "passive"))
    )
    (net (code "43") (name "/TSSP1") (class "Default")
      (node (ref "J10") (pin "1") (pinfunction "1_1") (pintype "passive"))
      (node (ref "U5") (pin "40") (pinfunction "PC9_40") (pintype "bidirectional"))
    )
    (net (code "44") (name "/TSSP2") (class "Default")
      (node (ref "J10") (pin "2") (pinfunction "2_2") (pintype "passive"))
      (node (ref "U5") (pin "39") (pinfunction "PC8_39") (pintype "bidirectional"))
    )
    (net (code "45") (name "/TSSP3") (class "Default")
      (node (ref "J10") (pin "3") (pinfunction "3_3") (pintype "passive"))
      (node (ref "U5") (pin "38") (pinfunction "PC7_38") (pintype "bidirectional"))
    )
    (net (code "46") (name "/TSSP4") (class "Default")
      (node (ref "J10") (pin "4") (pinfunction "4_4") (pintype "passive"))
      (node (ref "U5") (pin "37") (pinfunction "PC6_37") (pintype "bidirectional"))
    )
    (net (code "47") (name "/TSSP5") (class "Default")
      (node (ref "J10") (pin "5") (pinfunction "5_5") (pintype "passive"))
      (node (ref "U5") (pin "36") (pinfunction "PB15_36") (pintype "bidirectional"))
    )
    (net (code "48") (name "/TSSP6") (class "Default")
      (node (ref "J10") (pin "6") (pinfunction "6_6") (pintype "passive"))
      (node (ref "U5") (pin "35") (pinfunction "PB14_35") (pintype "bidirectional"))
    )
    (net (code "49") (name "/TSSP7") (class "Default")
      (node (ref "J10") (pin "7") (pinfunction "7_7") (pintype "passive"))
      (node (ref "U5") (pin "27") (pinfunction "PB1_27") (pintype "bidirectional"))
    )
    (net (code "50") (name "/TSSP8") (class "Default")
      (node (ref "J10") (pin "8") (pinfunction "8_8") (pintype "passive"))
      (node (ref "U5") (pin "26") (pinfunction "PB0_26") (pintype "bidirectional"))
    )
    (net (code "51") (name "/TSSP9") (class "Default")
      (node (ref "J10") (pin "9") (pinfunction "9_9") (pintype "passive"))
      (node (ref "U5") (pin "17") (pinfunction "PA3_17") (pintype "bidirectional"))
    )
    (net (code "52") (name "/TSSP10") (class "Default")
      (node (ref "J10") (pin "10") (pinfunction "10_10") (pintype "passive"))
      (node (ref "U5") (pin "16") (pinfunction "PA2_16") (pintype "bidirectional"))
    )
    (net (code "53") (name "/TSSP11") (class "Default")
      (node (ref "J10") (pin "11") (pinfunction "11_11") (pintype "passive"))
      (node (ref "U5") (pin "15") (pinfunction "PA1_15") (pintype "bidirectional"))
    )
    (net (code "54") (name "/TSSP12") (class "Default")
      (node (ref "J10") (pin "12") (pinfunction "12_12") (pintype "passive"))
      (node (ref "U5") (pin "14") (pinfunction "PA0-WKUP(PA0)_14") (pintype "bidirectional"))
    )
    (net (code "55") (name "/TSSP13") (class "Default")
      (node (ref "J10") (pin "13") (pinfunction "13_13") (pintype "passive"))
      (node (ref "U5") (pin "57") (pinfunction "PB5_57") (pintype "bidirectional"))
    )
    (net (code "56") (name "/TSSP14") (class "Default")
      (node (ref "J10") (pin "14") (pinfunction "14_14") (pintype "passive"))
      (node (ref "U5") (pin "56") (pinfunction "PB4(NJTRST)_56") (pintype "bidirectional"))
    )
    (net (code "57") (name "/TSSP15") (class "Default")
      (node (ref "J10") (pin "15") (pinfunction "15_15") (pintype "passive"))
      (node (ref "U5") (pin "55") (pinfunction "PB3(JTDO/TRACESWO)_55") (pintype "bidirectional"))
    )
    (net (code "58") (name "/TSSP16") (class "Default")
      (node (ref "J10") (pin "16") (pinfunction "16_16") (pintype "passive"))
      (node (ref "U5") (pin "50") (pinfunction "PA15(JTDI)_50") (pintype "bidirectional"))
    )
    (net (code "59") (name "GND") (class "Default")
      (node (ref "*") (pin "5") (pinfunction "SR_5") (pintype "passive"))
      (node (ref "*") (pin "6") (pinfunction "SI_6") (pintype "passive"))
      (node (ref "*") (pin "7") (pinfunction "GND_7") (pintype "passive"))
      (node (ref "C1") (pin "2") (pinfunction "-_2") (pintype "passive"))
      (node (ref "C12") (pin "2") (pinfunction "-_2") (pintype "passive"))
      (node (ref "C13") (pin "2") (pinfunction "2_2") (pintype "passive"))
      (node (ref "C14") (pin "2") (pinfunction "2_2") (pintype "passive"))
      (node (ref "C2") (pin "2") (pinfunction "2_2") (pintype "passive"))
      (node (ref "C20") (pin "1") (pinfunction "+_1") (pintype "passive"))
      (node (ref "C25") (pin "2") (pinfunction "-_2") (pintype "passive"))
      (node (ref "C26") (pin "2") (pinfunction "2_2") (pintype "passive"))
      (node (ref "C27") (pin "2") (pinfunction "2_2") (pintype "passive"))
      (node (ref "C28") (pin "2") (pinfunction "-_2") (pintype "passive"))
      (node (ref "C29") (pin "2") (pinfunction "-_2") (pintype "passive"))
      (node (ref "C3") (pin "2") (pinfunction "2_2") (pintype "passive"))
      (node (ref "C30") (pin "2") (pinfunction "-_2") (pintype "passive"))
      (node (ref "C31") (pin "2") (pinfunction "-_2") (pintype "passive"))
      (node (ref "C32") (pin "2") (pinfunction "-_2") (pintype "passive"))
      (node (ref "C33") (pin "2") (pinfunction "-_2") (pintype "passive"))
      (node (ref "C34") (pin "2") (pinfunction "-_2") (pintype "passive"))
      (node (ref "C35") (pin "2") (pinfunction "-_2") (pintype "passive"))
      (node (ref "C36") (pin "2") (pinfunction "-_2") (pintype "passive"))
      (node (ref "C37") (pin "1") (pinfunction "+_1") (pintype "passive"))
      (node (ref "C38") (pin "2") (pinfunction "-_2") (pintype "passive"))
      (node (ref "C39") (pin "2") (pinfunction "-_2") (pintype "passive"))
      (node (ref "C4") (pin "2") (pinfunction "2_2") (pintype "passive"))
      (node (ref "C5") (pin "2") (pinfunction "-_2") (pintype "passive"))
      (node (ref "C6") (pin "1") (pinfunction "+_1") (pintype "passive"))
      (node (ref "CAM") (pin "4") (pinfunction "4_4") (pintype "passive"))
      (node (ref "Ck") (pin "1") (pinfunction "+_1") (pintype "passive"))
      (node (ref "EM") (pin "1") (pinfunction "A0_1") (pintype "passive"))
      (node (ref "EM") (pin "2") (pinfunction "A1_2") (pintype "passive"))
      (node (ref "EM") (pin "3") (pinfunction "A2_3") (pintype "passive"))
      (node (ref "EM") (pin "4") (pinfunction "GND_4") (pintype "passive"))
      (node (ref "EM") (pin "7") (pinfunction "WP_7") (pintype "passive"))
      (node (ref "I1") (pin "3") (pinfunction "3_3") (pintype "passive"))
      (node (ref "I2C-4") (pin "3") (pinfunction "3_3") (pintype "passive"))
      (node (ref "J10") (pin "20") (pinfunction "20_20") (pintype "passive"))
      (node (ref "J7") (pin "4") (pinfunction "4_4") (pintype "passive"))
      (node (ref "J9") (pin "2") (pinfunction "2_2") (pintype "passive"))
      (node (ref "OLED") (pin "1") (pinfunction "1_1") (pintype "passive"))
      (node (ref "P1") (pin "1") (pinfunction "1_1") (pintype "passive"))
      (node (ref "POWER") (pin "2") (pinfunction "2_2") (pintype "passive"))
      (node (ref "POWER") (pin "3") (pinfunction "3_3") (pintype "passive"))
      (node (ref "Q1") (pin "1") (pinfunction "B_1") (pintype "passive"))
      (node (ref "Q2") (pin "1") (pinfunction "B_1") (pintype "passive"))
      (node (ref "Q3") (pin "1") (pinfunction "B_1") (pintype "passive"))
      (node (ref "Q4") (pin "1") (pinfunction "B_1") (pintype "passive"))
      (node (ref "Q7") (pin "1") (pinfunction "B_1") (pintype "passive"))
      (node (ref "R1") (pin "2") (pinfunction "2_2") (pintype "passive"))
      (node (ref "R10") (pin "1") (pinfunction "1_1") (pintype "passive"))
      (node (ref "R17") (pin "1") (pinfunction "1_1") (pintype "passive"))
      (node (ref "R20") (pin "1") (pinfunction "1_1") (pintype "passive"))
      (node (ref "R21") (pin "1") (pinfunction "1_1") (pintype "passive"))
      (node (ref "R37") (pin "2") (pinfunction "2_2") (pintype "passive"))
      (node (ref "R38") (pin "2") (pinfunction "2_2") (pintype "passive"))
      (node (ref "R39") (pin "2") (pinfunction "2_2") (pintype "passive"))
      (node (ref "R42") (pin "1") (pinfunction "1_1") (pintype "passive"))
      (node (ref "R43") (pin "1") (pinfunction "1_1") (pintype "passive"))
      (node (ref "R44") (pin "1") (pinfunction "1_1") (pintype "passive"))
      (node (ref "R45") (pin "1") (pinfunction "1_1") (pintype "passive"))
      (node (ref "R46") (pin "1") (pinfunction "1_1") (pintype "passive"))
      (node (ref "R48") (pin "1") (pinfunction "1_1") (pintype "passive"))
      (node (ref "R9") (pin "1") (pinfunction "1_1") (pintype "passive"))
      (node (ref "RI1A") (pin "2") (pinfunction "2_2") (pintype "passive"))
      (node (ref "RI2A") (pin "1") (pinfunction "1_1") (pintype "passive"))
      (node (ref "RI3A") (pin "2") (pinfunction "2_2") (pintype "passive"))
      (node (ref "RI4A") (pin "2") (pinfunction "2_2") (pintype "passive"))
      (node (ref "S18") (pin "2") (pinfunction "2_2") (pintype "passive"))
      (node (ref "S19") (pin "2") (pinfunction "2_2") (pintype "passive"))
      (node (ref "S20") (pin "1") (pinfunction "1_1") (pintype "passive"))
      (node (ref "SRF1") (pin "2") (pinfunction "2_2") (pintype "passive"))
      (node (ref "SRF2") (pin "2") (pinfunction "2_2") (pintype "passive"))
      (node (ref "SRF3") (pin "2") (pinfunction "2_2") (pintype "passive"))
      (node (ref "TVS") (pin "1") (pinfunction "A_1") (pintype "passive"))
      (node (ref "TVS1") (pin "1") (pinfunction "A_1") (pintype "passive"))
      (node (ref "U1") (pin "13") (pinfunction "GND_13") (pintype "power_in"))
      (node (ref "U1") (pin "21") (pinfunction "GND_21") (pintype "power_in"))
      (node (ref "U1") (pin "22") (pinfunction "GND_22") (pintype "power_in"))
      (node (ref "U2") (pin "2") (pinfunction "GND_2") (pintype "passive"))
      (node (ref "U3") (pin "2") (pinfunction "GND_2") (pintype "passive"))
      (node (ref "U4") (pin "1") (pinfunction "GND_1") (pintype "passive"))
      (node (ref "U5") (pin "12") (pinfunction "VSSA_12") (pintype "power_in"))
      (node (ref "U5") (pin "18") (pinfunction "VSS_18") (pintype "power_in"))
      (node (ref "U5") (pin "63") (pinfunction "VSS_63") (pintype "power_in"))
      (node (ref "W") (pin "2") (pinfunction "2_2") (pintype "passive"))
      (node (ref "W") (pin "5") (pinfunction "5_5") (pintype "passive"))
      (node (ref "X1") (pin "2") (pinfunction "2_2") (pintype "passive"))
      (node (ref "X1") (pin "4") (pinfunction "4_4") (pintype "passive"))
    )
    (net (code "60") (name "LED1") (class "Default")
      (node (ref "D5") (pin "1") (pinfunction "A_1") (pintype "passive"))
      (node (ref "U5") (pin "3") (pinfunction "PC14-OSC32_IN(PC14)_3") (pintype "bidirectional"))
    )
    (net (code "61") (name "M-STBY") (class "Default")
      (node (ref "J1") (pin "1") (pinfunction "1_1") (pintype "passive"))
      (node (ref "J2") (pin "1") (pinfunction "1_1") (pintype "passive"))
      (node (ref "J5") (pin "1") (pinfunction "1_1") (pintype "passive"))
      (node (ref "J6") (pin "1") (pinfunction "1_1") (pintype "passive"))
      (node (ref "R1") (pin "1") (pinfunction "1_1") (pintype "passive"))
      (node (ref "U5") (pin "24") (pinfunction "PC4_24") (pintype "bidirectional"))
    )
    (net (code "62") (name "Net-(C19--)") (class "Default")
      (node (ref "C19") (pin "2") (pinfunction "-_2") (pintype "passive"))
      (node (ref "C20") (pin "2") (pinfunction "-_2") (pintype "passive"))
    )
    (net (code "63") (name "Net-(D1-K)") (class "Default")
      (node (ref "D1") (pin "2") (pinfunction "K_2") (pintype "passive"))
      (node (ref "R9") (pin "2") (pinfunction "2_2") (pintype "passive"))
    )
    (net (code "64") (name "Net-(D2-A)") (class "Default")
      (node (ref "D2") (pin "1") (pinfunction "A_1") (pintype "passive"))
      (node (ref "U1") (pin "31") (pinfunction "PIO[8]_31") (pintype "bidirectional"))
    )
    (net (code "65") (name "Net-(D2-K)") (class "Default")
      (node (ref "D2") (pin "2") (pinfunction "K_2") (pintype "passive"))
      (node (ref "R10") (pin "2") (pinfunction "2_2") (pintype "passive"))
    )
    (net (code "66") (name "Net-(D3-A)") (class "Default")
      (node (ref "D3") (pin "1") (pinfunction "A_1") (pintype "passive"))
      (node (ref "U1") (pin "32") (pinfunction "PIO[9]_32") (pintype "bidirectional"))
    )
    (net (code "67") (name "Net-(D3-K)") (class "Default")
      (node (ref "D3") (pin "2") (pinfunction "K_2") (pintype "passive"))
      (node (ref "R17") (pin "2") (pinfunction "2_2") (pintype "passive"))
    )
    (net (code "68") (name "Net-(D4-K)") (class "Default")
      (node (ref "D4") (pin "2") (pinfunction "K_2") (pintype "passive"))
      (node (ref "R20") (pin "2") (pinfunction "2_2") (pintype "passive"))
    )
    (net (code "69") (name "Net-(D5-K)") (class "Default")
      (node (ref "D5") (pin "2") (pinfunction "K_2") (pintype "passive"))
      (node (ref "R42") (pin "2") (pinfunction "2_2") (pintype "passive"))
    )
    (net (code "70") (name "Net-(D6-K)") (class "Default")
      (node (ref "D6") (pin "2") (pinfunction "K_2") (pintype "passive"))
      (node (ref "R44") (pin "2") (pinfunction "2_2") (pintype "passive"))
    )
    (net (code "71") (name "Net-(D7-K)") (class "Default")
      (node (ref "D7") (pin "2") (pinfunction "K_2") (pintype "passive"))
      (node (ref "R43") (pin "2") (pinfunction "2_2") (pintype "passive"))
    )
    (net (code "72") (name "Net-(D8-K)") (class "Default")
      (node (ref "D8") (pin "2") (pinfunction "K_2") (pintype "passive"))
      (node (ref "R46") (pin "2") (pinfunction "2_2") (pintype "passive"))
    )
    (net (code "73") (name "Net-(D9-K)") (class "Default")
      (node (ref "D9") (pin "2") (pinfunction "K_2") (pintype "passive"))
      (node (ref "R45") (pin "2") (pinfunction "2_2") (pintype "passive"))
    )
    (net (code "74") (name "Net-(D10-K)") (class "Default")
      (node (ref "D10") (pin "2") (pinfunction "K_2") (pintype "passive"))
      (node (ref "R48") (pin "2") (pinfunction "2_2") (pintype "passive"))
    )
    (net (code "75") (name "Net-(EM-SCL)") (class "Default")
      (node (ref "EM") (pin "6") (pinfunction "SCL_6") (pintype "passive"))
      (node (ref "EM-J") (pin "2") (pinfunction "2_2") (pintype "passive"))
    )
    (net (code "76") (name "Net-(EM-SDA)") (class "Default")
      (node (ref "EM") (pin "5") (pinfunction "SDA_5") (pintype "passive"))
      (node (ref "EM-J") (pin "3") (pinfunction "3_3") (pintype "passive"))
    )
    (net (code "77") (name "Net-(J10-Pad18)") (class "Default")
      (node (ref "J10") (pin "18") (pinfunction "18_18") (pintype "passive"))
      (node (ref "J11") (pin "2") (pinfunction "2_2") (pintype "passive"))
    )
    (net (code "78") (name "Net-(Q5-C)") (class "Default")
      (node (ref "CAM") (pin "1") (pinfunction "1_1") (pintype "passive"))
      (node (ref "Q5") (pin "3") (pinfunction "C_3") (pintype "passive"))
      (node (ref "R18") (pin "2") (pinfunction "2_2") (pintype "passive"))
    )
    (net (code "79") (name "Net-(Q6-C)") (class "Default")
      (node (ref "CAM") (pin "3") (pinfunction "3_3") (pintype "passive"))
      (node (ref "Q6") (pin "3") (pinfunction "C_3") (pintype "passive"))
      (node (ref "R22") (pin "1") (pinfunction "1_1") (pintype "passive"))
    )
    (net (code "80") (name "Net-(Q7-C)") (class "Default")
      (node (ref "J11") (pin "3") (pinfunction "3_3") (pintype "passive"))
      (node (ref "Q7") (pin "3") (pinfunction "C_3") (pintype "passive"))
    )
    (net (code "81") (name "Net-(R29-Pad1)") (class "Default")
      (node (ref "R29") (pin "1") (pinfunction "1_1") (pintype "passive"))
      (node (ref "SRF1") (pin "3") (pinfunction "3_3") (pintype "passive"))
    )
    (net (code "82") (name "Net-(R30-Pad1)") (class "Default")
      (node (ref "R30") (pin "1") (pinfunction "1_1") (pintype "passive"))
      (node (ref "SRF2") (pin "3") (pinfunction "3_3") (pintype "passive"))
    )
    (net (code "83") (name "Net-(R31-Pad1)") (class "Default")
      (node (ref "R31") (pin "1") (pinfunction "1_1") (pintype "passive"))
      (node (ref "SRF3") (pin "3") (pinfunction "3_3") (pintype "passive"))
    )
    (net (code "84") (name "Net-(U1-PIO[11])") (class "Default")
      (node (ref "R21") (pin "2") (pinfunction "2_2") (pintype "passive"))
      (node (ref "S13") (pin "2") (pinfunction "2_2") (pintype "passive"))
      (node (ref "U1") (pin "34") (pinfunction "PIO[11]_34") (pintype "bidirectional"))
    )
    (net (code "85") (name "Net-(U1-UART-RX)") (class "Default")
      (node (ref "J3") (pin "2") (pinfunction "2_2") (pintype "passive"))
      (node (ref "J4") (pin "4") (pinfunction "4_4") (pintype "passive"))
      (node (ref "U1") (pin "2") (pinfunction "UART-RX_2") (pintype "input"))
    )
    (net (code "86") (name "Net-(U1-UART-TX)") (class "Default")
      (node (ref "J3") (pin "1") (pinfunction "1_1") (pintype "passive"))
      (node (ref "J4") (pin "3") (pinfunction "3_3") (pintype "passive"))
      (node (ref "U1") (pin "1") (pinfunction "UART-TX_1") (pintype "output"))
    )
    (net (code "87") (name "O-LED1") (class "Default")
      (node (ref "D9") (pin "1") (pinfunction "A_1") (pintype "passive"))
      (node (ref "OT") (pin "1") (pinfunction "1_1") (pintype "passive"))
    )
    (net (code "88") (name "O-LED2") (class "Default")
      (node (ref "D10") (pin "1") (pinfunction "A_1") (pintype "passive"))
      (node (ref "OT") (pin "6") (pinfunction "6_6") (pintype "passive"))
    )
    (net (code "89") (name "O-LED3") (class "Default")
      (node (ref "D8") (pin "1") (pinfunction "A_1") (pintype "passive"))
      (node (ref "OT") (pin "2") (pinfunction "2_2") (pintype "passive"))
    )
    (net (code "90") (name "O-LED4") (class "Default")
      (node (ref "D7") (pin "1") (pinfunction "A_1") (pintype "passive"))
      (node (ref "OT") (pin "4") (pinfunction "4_4") (pintype "passive"))
    )
    (net (code "91") (name "PWM1") (class "Default")
      (node (ref "J1") (pin "4") (pinfunction "4_4") (pintype "passive"))
      (node (ref "U5") (pin "44") (pinfunction "PA11_44") (pintype "bidirectional"))
    )
    (net (code "92") (name "PWM2") (class "Default")
      (node (ref "J5") (pin "4") (pinfunction "4_4") (pintype "passive"))
      (node (ref "U5") (pin "43") (pinfunction "PA10_43") (pintype "bidirectional"))
    )
    (net (code "93") (name "PWM3") (class "Default")
      (node (ref "J2") (pin "4") (pinfunction "4_4") (pintype "passive"))
      (node (ref "U5") (pin "42") (pinfunction "PA9_42") (pintype "bidirectional"))
    )
    (net (code "94") (name "PWM4") (class "Default")
      (node (ref "J6") (pin "4") (pinfunction "4_4") (pintype "passive"))
      (node (ref "U5") (pin "41") (pinfunction "PA8_41") (pintype "bidirectional"))
    )
    (net (code "95") (name "VCAP1") (class "Default")
      (node (ref "C34") (pin "1") (pinfunction "+_1") (pintype "passive"))
      (node (ref "U5") (pin "31") (pinfunction "VCAP_1_31") (pintype "power_in"))
    )
    (net (code "96") (name "VCAP2") (class "Default")
      (node (ref "C35") (pin "1") (pinfunction "+_1") (pintype "passive"))
      (node (ref "U5") (pin "47") (pinfunction "VCAP_2_47") (pintype "power_in"))
    )
    (net (code "97") (name "unconnected-(*-ADD-Pad3)") (class "Default")
      (node (ref "*") (pin "3") (pinfunction "ADD_3") (pintype "passive+no_connect"))
    )
    (net (code "98") (name "unconnected-(*-RX-Pad8)") (class "Default")
      (node (ref "*") (pin "8") (pinfunction "RX_8") (pintype "passive+no_connect"))
    )
    (net (code "99") (name "unconnected-(*-Reset-Pad4)") (class "Default")
      (node (ref "*") (pin "4") (pinfunction "Reset_4") (pintype "passive+no_connect"))
    )
    (net (code "100") (name "unconnected-(*-TX-Pad9)") (class "Default")
      (node (ref "*") (pin "9") (pinfunction "TX_9") (pintype "passive+no_connect"))
    )
    (net (code "101") (name "unconnected-(U1-AIO[0]-Pad9)") (class "Default")
      (node (ref "U1") (pin "9") (pinfunction "AIO[0]_9") (pintype "bidirectional+no_connect"))
    )
    (net (code "102") (name "unconnected-(U1-AIO[1]-Pad10)") (class "Default")
      (node (ref "U1") (pin "10") (pinfunction "AIO[1]_10") (pintype "bidirectional+no_connect"))
    )
    (net (code "103") (name "unconnected-(U1-PCM-CLK-Pad5)") (class "Default")
      (node (ref "U1") (pin "5") (pinfunction "PCM-CLK_5") (pintype "bidirectional+no_connect"))
    )
    (net (code "104") (name "unconnected-(U1-PCM-IN-Pad7)") (class "Default")
      (node (ref "U1") (pin "7") (pinfunction "PCM-IN_7") (pintype "input+no_connect"))
    )
    (net (code "105") (name "unconnected-(U1-PCM-OUT-Pad6)") (class "Default")
      (node (ref "U1") (pin "6") (pinfunction "PCM-OUT_6") (pintype "output+no_connect"))
    )
    (net (code "106") (name "unconnected-(U1-PCN-SYNC-Pad8)") (class "Default")
      (node (ref "U1") (pin "8") (pinfunction "PCN-SYNC_8") (pintype "bidirectional+no_connect"))
    )
    (net (code "107") (name "unconnected-(U1-PIO[0]-Pad23)") (class "Default")
      (node (ref "U1") (pin "23") (pinfunction "PIO[0]_23") (pintype "bidirectional+no_connect"))
    )
    (net (code "108") (name "unconnected-(U1-PIO[1]-Pad24)") (class "Default")
      (node (ref "U1") (pin "24") (pinfunction "PIO[1]_24") (pintype "bidirectional+no_connect"))
    )
    (net (code "109") (name "unconnected-(U1-PIO[2]-Pad25)") (class "Default")
      (node (ref "U1") (pin "25") (pinfunction "PIO[2]_25") (pintype "bidirectional+no_connect"))
    )
    (net (code "110") (name "unconnected-(U1-PIO[3]-Pad26)") (class "Default")
      (node (ref "U1") (pin "26") (pinfunction "PIO[3]_26") (pintype "bidirectional+no_connect"))
    )
    (net (code "111") (name "unconnected-(U1-PIO[4]-Pad27)") (class "Default")
      (node (ref "U1") (pin "27") (pinfunction "PIO[4]_27") (pintype "bidirectional+no_connect"))
    )
    (net (code "112") (name "unconnected-(U1-PIO[5]-Pad28)") (class "Default")
      (node (ref "U1") (pin "28") (pinfunction "PIO[5]_28") (pintype "bidirectional+no_connect"))
    )
    (net (code "113") (name "unconnected-(U1-PIO[6]-Pad29)") (class "Default")
      (node (ref "U1") (pin "29") (pinfunction "PIO[6]_29") (pintype "bidirectional+no_connect"))
    )
    (net (code "114") (name "unconnected-(U1-PIO[7]-Pad30)") (class "Default")
      (node (ref "U1") (pin "30") (pinfunction "PIO[7]_30") (pintype "bidirectional+no_connect"))
    )
    (net (code "115") (name "unconnected-(U1-PIO[10]-Pad33)") (class "Default")
      (node (ref "U1") (pin "33") (pinfunction "PIO[10]_33") (pintype "bidirectional+no_connect"))
    )
    (net (code "116") (name "unconnected-(U1-SPI_CLK-Pad19)") (class "Default")
      (node (ref "U1") (pin "19") (pinfunction "SPI_CLK_19") (pintype "input+no_connect"))
    )
    (net (code "117") (name "unconnected-(U1-SPI_MISO-Pad18)") (class "Default")
      (node (ref "U1") (pin "18") (pinfunction "SPI_MISO_18") (pintype "output+no_connect"))
    )
    (net (code "118") (name "unconnected-(U1-SPI_MOSI-Pad17)") (class "Default")
      (node (ref "U1") (pin "17") (pinfunction "SPI_MOSI_17") (pintype "input+no_connect"))
    )
    (net (code "119") (name "unconnected-(U1-USB_+-Pad20)") (class "Default")
      (node (ref "U1") (pin "20") (pinfunction "USB_+_20") (pintype "bidirectional+no_connect"))
    )
    (net (code "120") (name "unconnected-(U1-USB_--Pad15)") (class "Default")
      (node (ref "U1") (pin "15") (pinfunction "USB_-_15") (pintype "bidirectional+no_connect"))
    )
    (net (code "121") (name "unconnected-(U1-~{RESETB}-Pad11)") (class "Default")
      (node (ref "U1") (pin "11") (pinfunction "~{RESETB}_11") (pintype "input+no_connect"))
    )
    (net (code "122") (name "unconnected-(U1-~{SPI_CSB}-Pad16)") (class "Default")
      (node (ref "U1") (pin "16") (pinfunction "~{SPI_CSB}_16") (pintype "input+no_connect"))
    )
    (net (code "123") (name "unconnected-(U1-~{UART-CTS}-Pad3)") (class "Default")
      (node (ref "U1") (pin "3") (pinfunction "~{UART-CTS}_3") (pintype "input+no_connect"))
    )
    (net (code "124") (name "unconnected-(U1-~{UART-RTS}-Pad4)") (class "Default")
      (node (ref "U1") (pin "4") (pinfunction "~{UART-RTS}_4") (pintype "output+no_connect"))
    )
    (net (code "125") (name "unconnected-(U5B-VBAT-Pad1)") (class "Default")
      (node (ref "U5") (pin "1") (pinfunction "VBAT_1") (pintype "power_in+no_connect"))
    )
    (net (code "126") (name "unconnected-(W-Pad3)") (class "Default")
      (node (ref "W") (pin "3") (pinfunction "3_3") (pintype "passive+no_connect"))
    )
    (net (code "127") (name "unconnected-(W-Pad6)") (class "Default")
      (node (ref "W") (pin "6") (pinfunction "6_6") (pintype "passive+no_connect"))
    )
  )
)
